# CIRCUIT_PRIMAIRE.net
KiCad netlist of a schematic drawn in Altium Designer
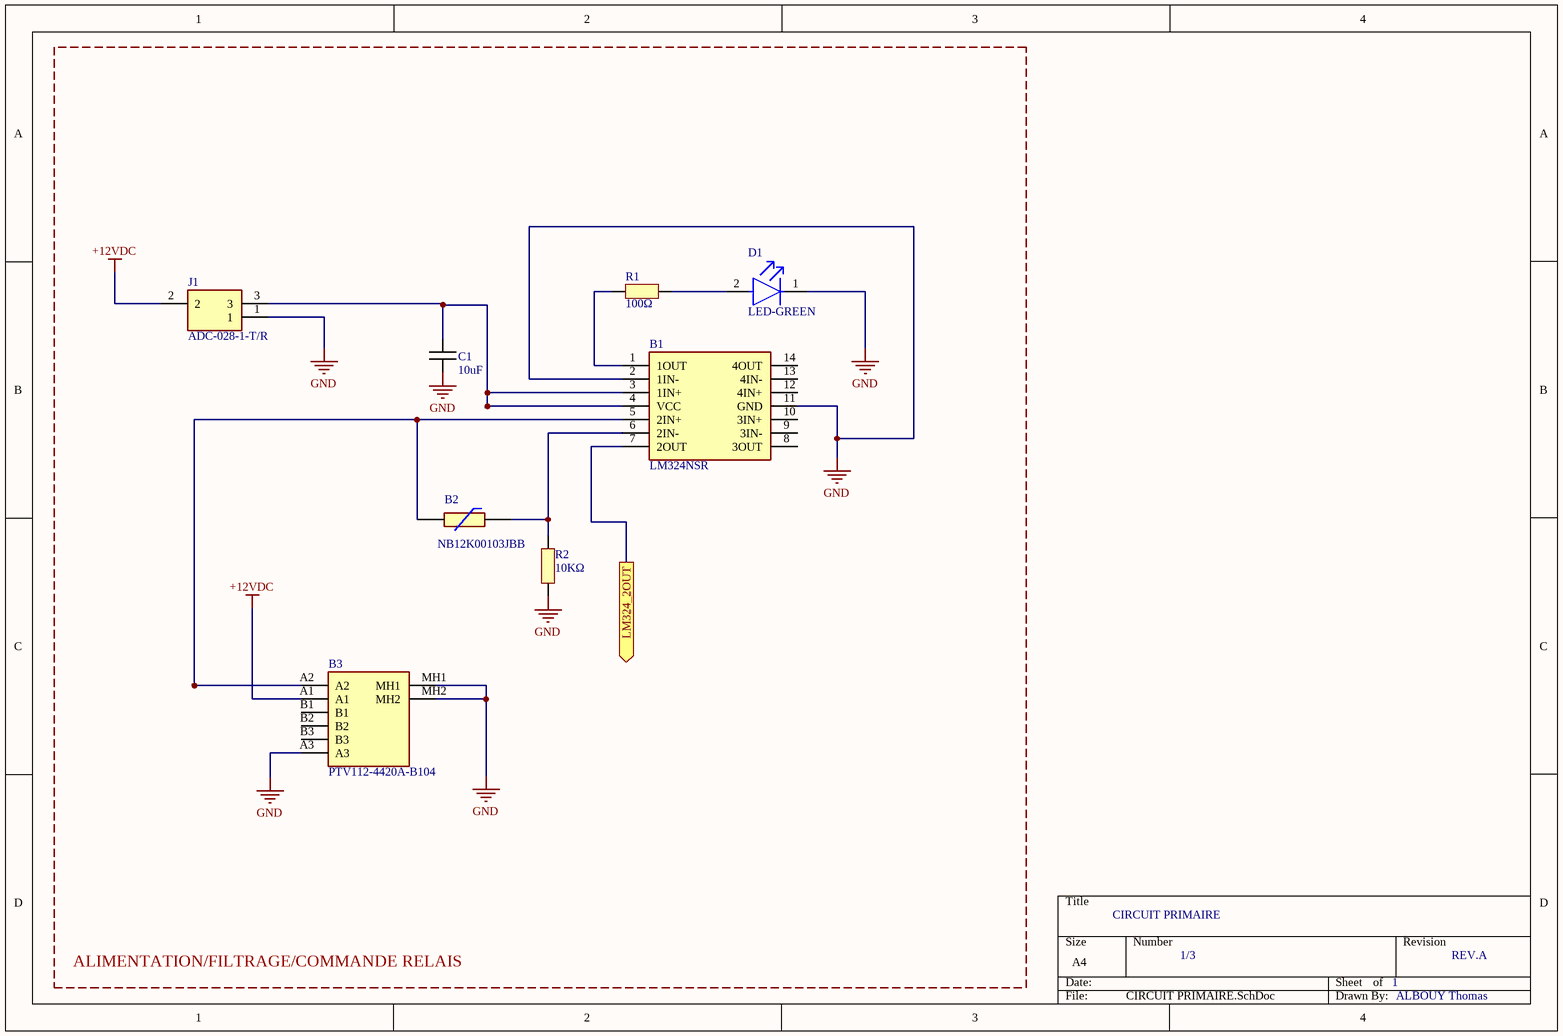
[diagram p0: CIRCUIT PRIMAIRE.SchDoc]

(export (version "E")
  (design (tool "Eeschema 10.0.6"))
  (components
    (comp (ref "B1")
      (value "LM324NSR")
      (footprint "SOIC127P780X200-14N")
      (description "Quadruple Operational Amplifier")
      (fields (field (name "MOUSER PART NUMBER") "595-LM324NSR"))
      (libsource (lib "Schlib1") (part "LM324NSR"))
    )
    (comp (ref "B2")
      (value "NB12K00103JBB")
      (footprint "RESC2212X50N")
      (description "NTC SMD Thermistor, NB12K, 10K, 5% AVX 10k 0805 Protection NTC Thermistor, 5s, 2 x 1.25 x 1.3mm")
      (fields (field (name "MOUSER PART NUMBER") "581-NB12K00103JBB"))
      (libsource (lib "Schlib1") (part "NB12K00103JBB"))
    )
    (comp (ref "B3")
      (value "PTV112-4420A-B104")
      (footprint "PTV1124420AB104")
      (description "Potentiometers PANEL CONTROL 100kOhm")
      (fields (field (name "MOUSER PART NUMBER") "652-PTV1124420AB104"))
      (libsource (lib "Schlib1") (part "PTV112-4420A-B104"))
    )
    (comp (ref "C1") (value "10uF") (footprint "CAPC1005X06N") (libsource (lib "Schlib1") (part "Capacitor")))
    (comp (ref "D1")
      (value "LED-GREEN")
      (footprint "SMD-1608-LED")
      (description "LED GREEN CLEAR CHIP SMD LTST-C190GKT")
      (fields (field (name "VOLTAGE") "2V"))
      (libsource (lib "Schlib1") (part "LED-GREEN"))
    )
    (comp (ref "J1")
      (value "ADC-028-1-T/R")
      (footprint "PJ1021SMTTR")
      (description "Connecteurs d'alimentation continue DC POWER JACK 2MM PIN TYPE 028")
      (fields (field (name "MOUSER PART NUMBER") "737-ADC-028-1-T/R"))
      (libsource (lib "Schlib1") (part "ADC-028-1-T/R"))
    )
    (comp (ref "R1") (value "100Ω") (footprint "RESC1005X06N") (libsource (lib "Schlib1") (part "Resistor")))
    (comp (ref "R2") (value "10KΩ") (footprint "RESC1005X06N") (libsource (lib "") (part "Resistor_1")))
  )
  (nets
    (net (code "1") (name "+12VDC") (class "Default")
      (node (ref "B3") (pin "A1") (pinfunction "A1_A1") (pintype "passive"))
      (node (ref "J1") (pin "2") (pinfunction "2_2") (pintype "passive"))
    )
    (net (code "2") (name "/LM324_2OUT") (class "Default")
      (node (ref "B1") (pin "7") (pinfunction "2OUT_7") (pintype "passive"))
    )
    (net (code "3") (name "GND") (class "Default")
      (node (ref "B1") (pin "11") (pinfunction "GND_11") (pintype "passive"))
      (node (ref "B1") (pin "2") (pinfunction "1IN-_2") (pintype "passive"))
      (node (ref "B3") (pin "A3") (pinfunction "A3_A3") (pintype "passive"))
      (node (ref "B3") (pin "MH1") (pinfunction "MH1_MH1") (pintype "passive"))
      (node (ref "B3") (pin "MH2") (pinfunction "MH2_MH2") (pintype "passive"))
      (node (ref "C1") (pin "2") (pinfunction "2_2") (pintype "passive"))
      (node (ref "D1") (pin "1") (pinfunction "C_1") (pintype "passive"))
      (node (ref "J1") (pin "1") (pinfunction "1_1") (pintype "passive"))
      (node (ref "R2") (pin "1") (pinfunction "1_1") (pintype "passive"))
    )
    (net (code "4") (name "Net-(B1-1IN+)") (class "Default")
      (node (ref "B1") (pin "3") (pinfunction "1IN+_3") (pintype "passive"))
      (node (ref "B1") (pin "4") (pinfunction "VCC_4") (pintype "passive"))
      (node (ref "C1") (pin "1") (pinfunction "1_1") (pintype "passive"))
      (node (ref "J1") (pin "3") (pinfunction "3_3") (pintype "passive"))
    )
    (net (code "5") (name "Net-(B1-1OUT)") (class "Default")
      (node (ref "B1") (pin "1") (pinfunction "1OUT_1") (pintype "passive"))
      (node (ref "R1") (pin "1") (pinfunction "1_1") (pintype "passive"))
    )
    (net (code "6") (name "Net-(B1-2IN+)") (class "Default")
      (node (ref "B1") (pin "5") (pinfunction "2IN+_5") (pintype "passive"))
      (node (ref "B2") (pin "2") (pinfunction "2_2") (pintype "passive"))
      (node (ref "B3") (pin "A2") (pinfunction "A2_A2") (pintype "passive"))
    )
    (net (code "7") (name "Net-(B1-2IN-)") (class "Default")
      (node (ref "B1") (pin "6") (pinfunction "2IN-_6") (pintype "passive"))
      (node (ref "B2") (pin "1") (pinfunction "1_1") (pintype "passive"))
      (node (ref "R2") (pin "2") (pinfunction "2_2") (pintype "passive"))
    )
    (net (code "8") (name "Net-(D1-A)") (class "Default")
      (node (ref "D1") (pin "2") (pinfunction "A_2") (pintype "passive"))
      (node (ref "R1") (pin "2") (pinfunction "2_2") (pintype "passive"))
    )
    (net (code "9") (name "unconnected-(B1-3IN+-Pad10)") (class "Default")
      (node (ref "B1") (pin "10") (pinfunction "3IN+_10") (pintype "passive"))
    )
    (net (code "10") (name "unconnected-(B1-3IN--Pad9)") (class "Default")
      (node (ref "B1") (pin "9") (pinfunction "3IN-_9") (pintype "passive"))
    )
    (net (code "11") (name "unconnected-(B1-3OUT-Pad8)") (class "Default")
      (node (ref "B1") (pin "8") (pinfunction "3OUT_8") (pintype "passive"))
    )
    (net (code "12") (name "unconnected-(B1-4IN+-Pad12)") (class "Default")
      (node (ref "B1") (pin "12") (pinfunction "4IN+_12") (pintype "passive"))
    )
    (net (code "13") (name "unconnected-(B1-4IN--Pad13)") (class "Default")
      (node (ref "B1") (pin "13") (pinfunction "4IN-_13") (pintype "passive"))
    )
    (net (code "14") (name "unconnected-(B1-4OUT-Pad14)") (class "Default")
      (node (ref "B1") (pin "14") (pinfunction "4OUT_14") (pintype "passive"))
    )
    (net (code "15") (name "unconnected-(B3-PadB1)") (class "Default")
      (node (ref "B3") (pin "B1") (pinfunction "B1_B1") (pintype "passive"))
    )
    (net (code "16") (name "unconnected-(B3-PadB2)") (class "Default")
      (node (ref "B3") (pin "B2") (pinfunction "B2_B2") (pintype "passive"))
    )
    (net (code "17") (name "unconnected-(B3-PadB3)") (class "Default")
      (node (ref "B3") (pin "B3") (pinfunction "B3_B3") (pintype "passive"))
    )
  )
)
